# DDR3L.net
KiCad netlist of a schematic drawn in Altium Designer
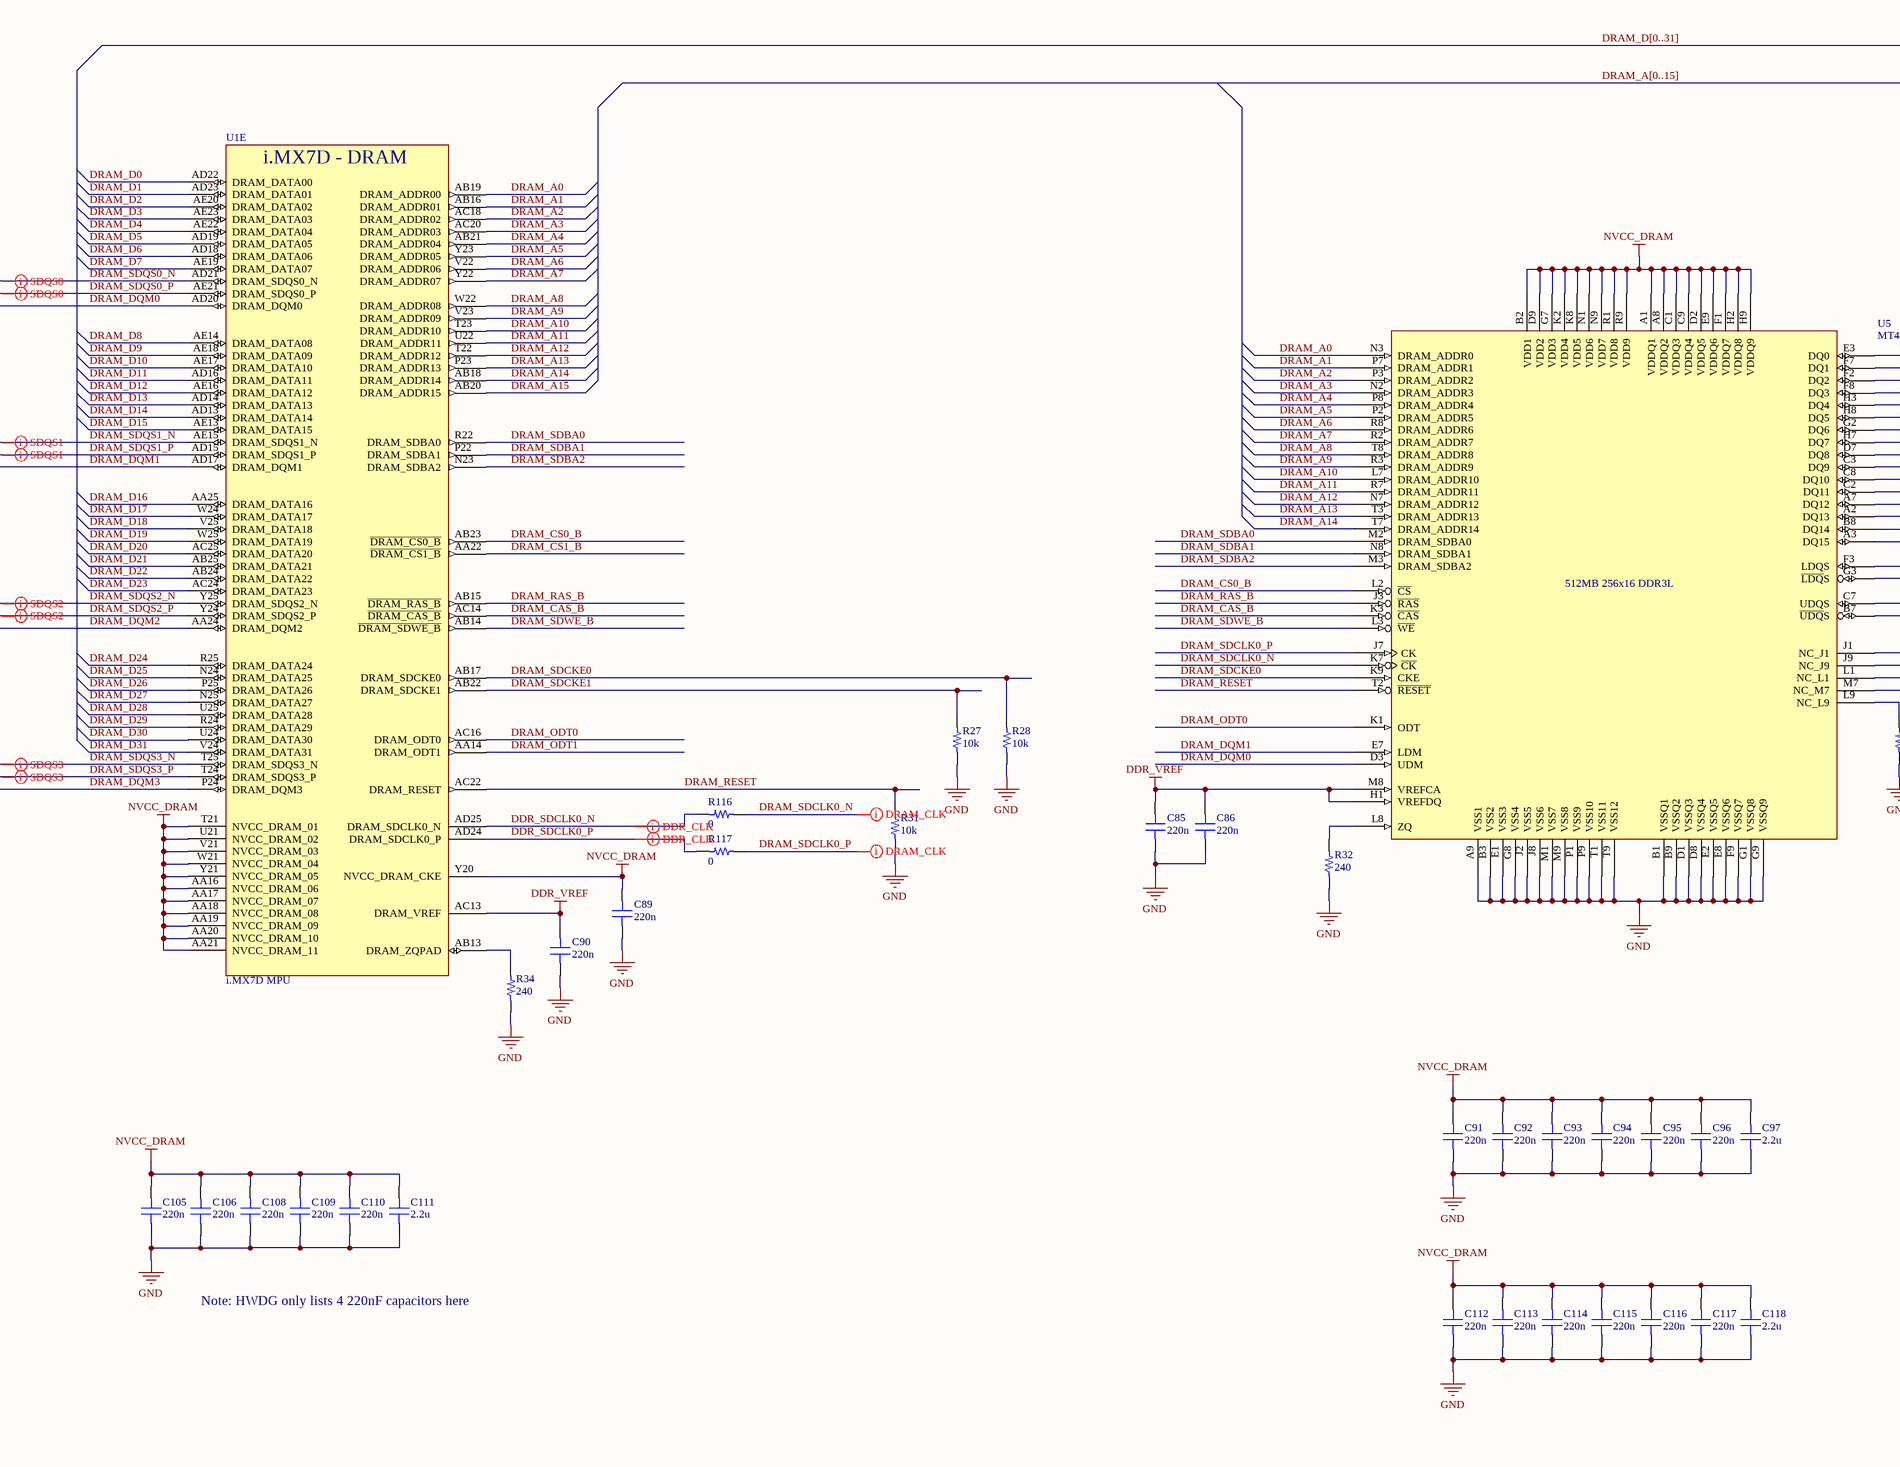
[diagram p0: DDR3L.SchDoc, left]
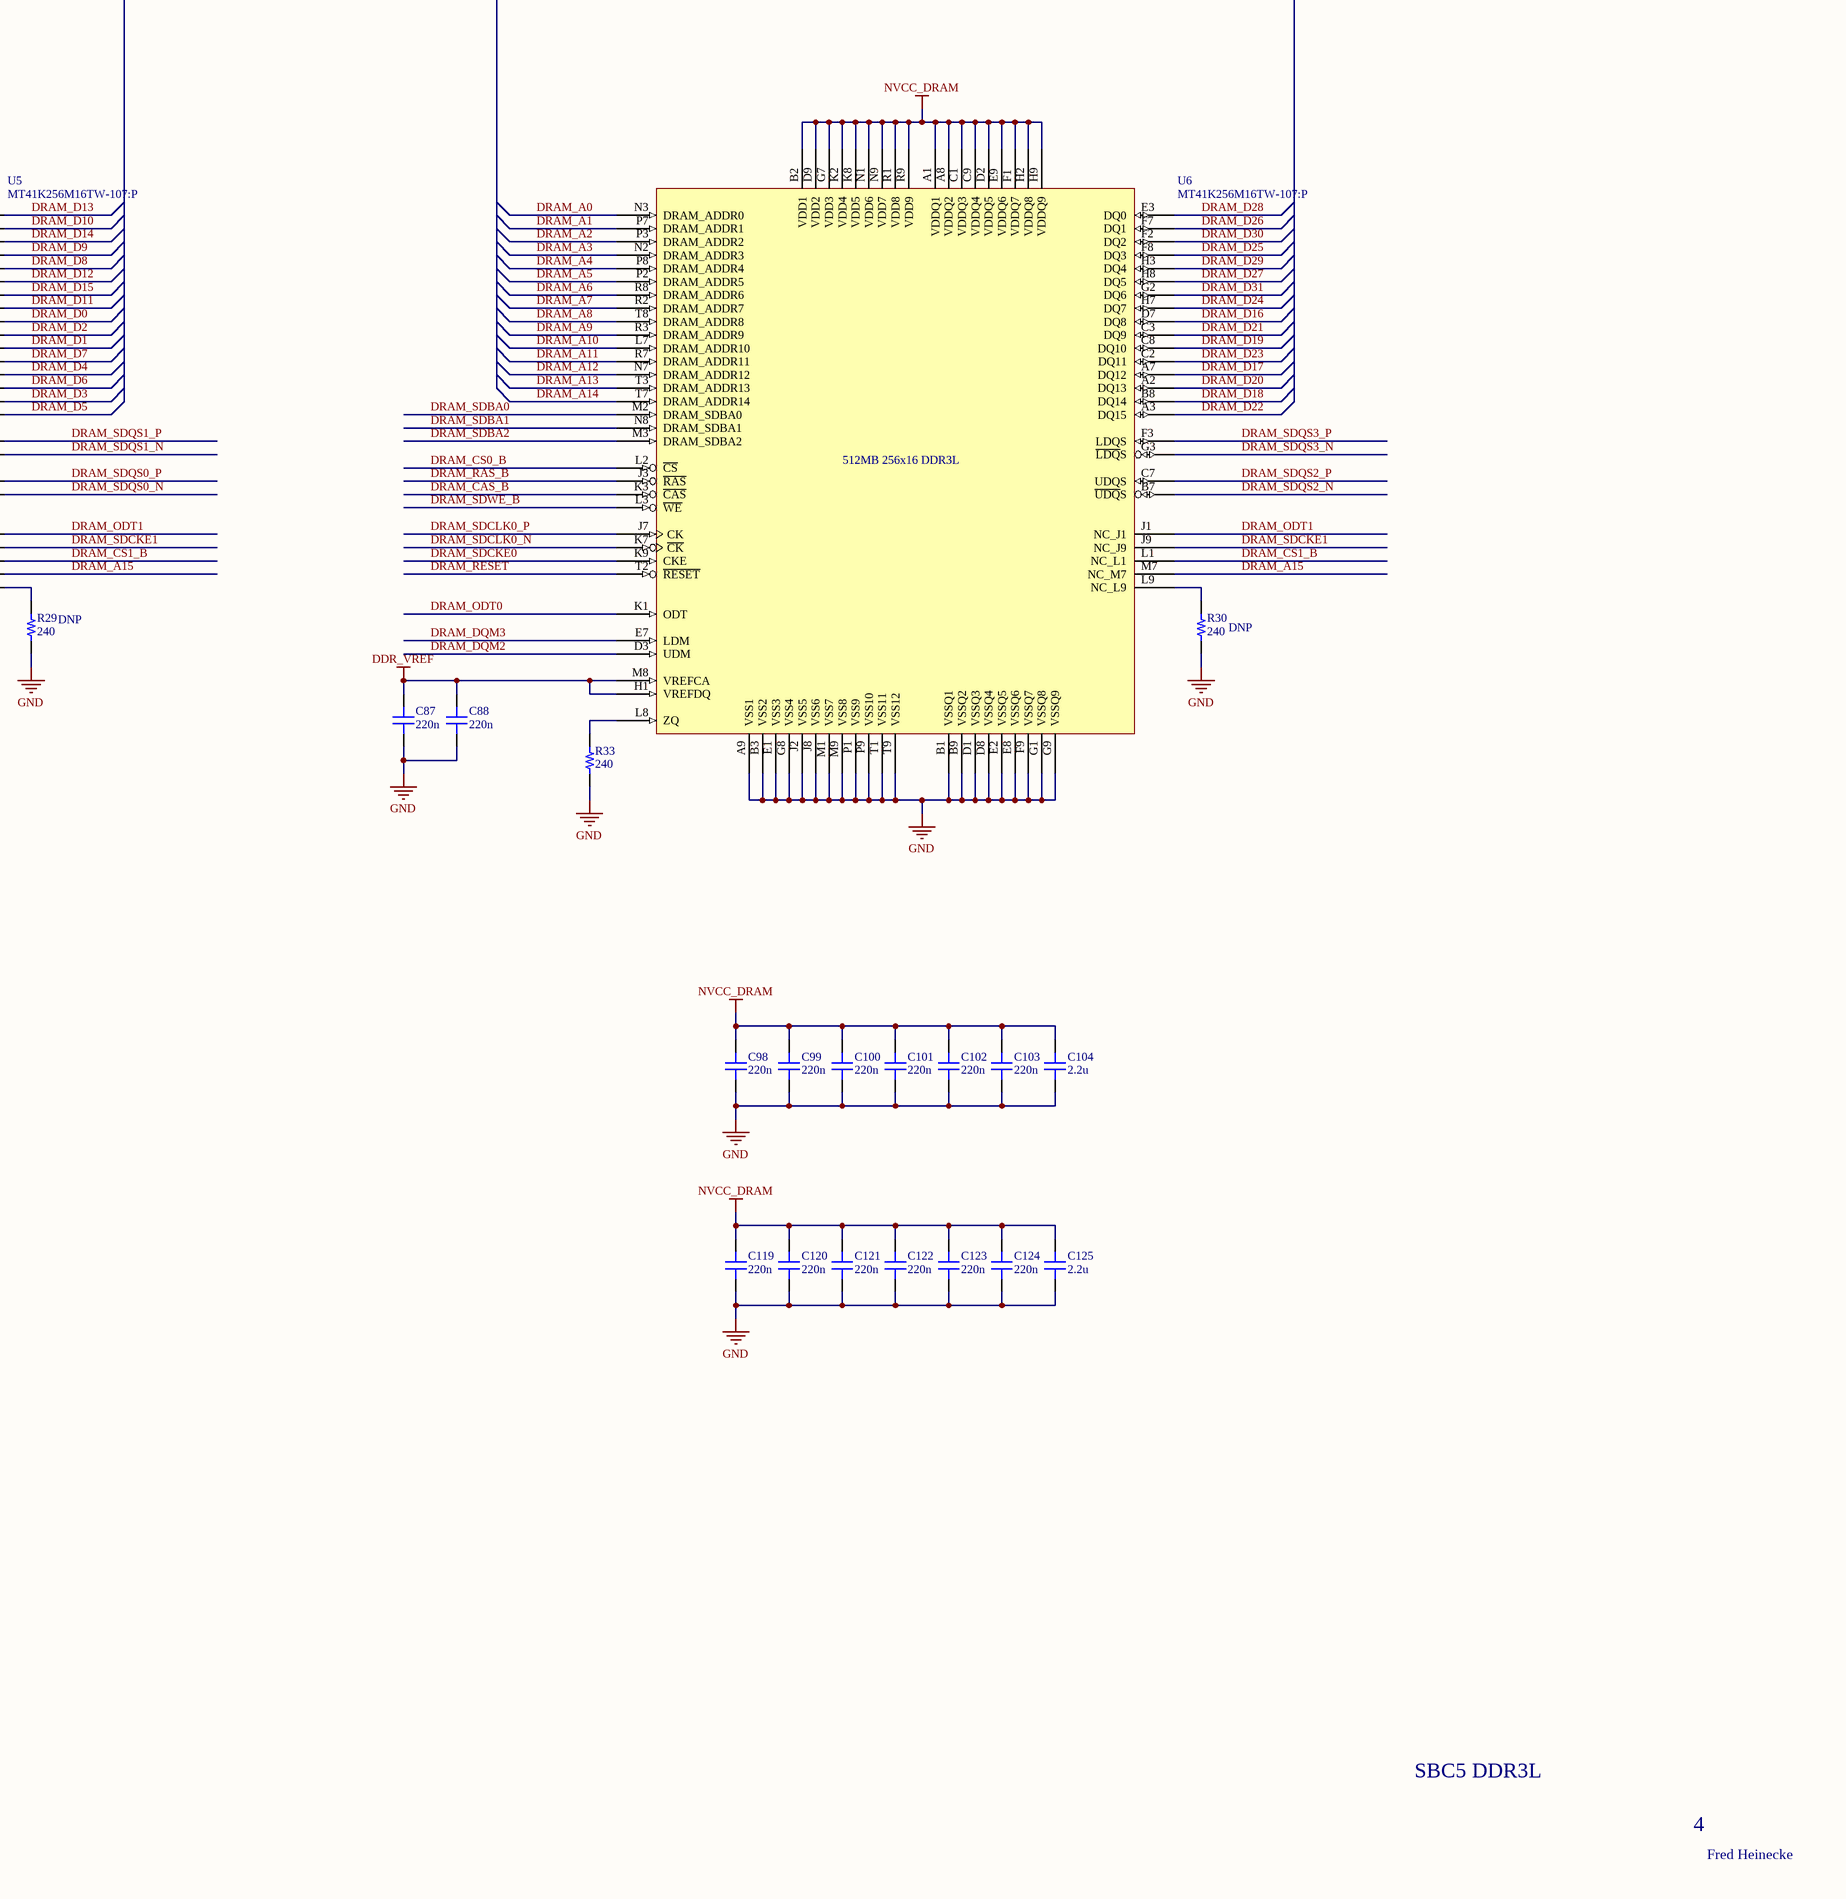
[diagram p1: DDR3L.SchDoc, right]

(export (version "E")
  (design (tool "Eeschema 10.0.6"))
  (components
    (comp (ref "C85")
      (value "220n")
      (footprint "C0201")
      (description "Cap Ceramic Monolithic 0.22uF 16VDC 10% SMD Paper T/R")
      (fields
        (field (name "MANUFACTURER") "Murata")
        (field (name "MANUFACTURER PART NUMBER") "GRM033R61C224KE14D")
      )
      (libsource (lib "SBC5") (part "GRM033R61C224KE14D"))
    )
    (comp (ref "C86")
      (value "220n")
      (footprint "C0201")
      (description "Cap Ceramic Monolithic 0.22uF 16VDC 10% SMD Paper T/R")
      (fields
        (field (name "MANUFACTURER") "Murata")
        (field (name "MANUFACTURER PART NUMBER") "GRM033R61C224KE14D")
      )
      (libsource (lib "SBC5") (part "GRM033R61C224KE14D"))
    )
    (comp (ref "C87")
      (value "220n")
      (footprint "C0201")
      (description "Cap Ceramic Monolithic 0.22uF 16VDC 10% SMD Paper T/R")
      (fields
        (field (name "MANUFACTURER") "Murata")
        (field (name "MANUFACTURER PART NUMBER") "GRM033R61C224KE14D")
      )
      (libsource (lib "SBC5") (part "GRM033R61C224KE14D"))
    )
    (comp (ref "C88")
      (value "220n")
      (footprint "C0201")
      (description "Cap Ceramic Monolithic 0.22uF 16VDC 10% SMD Paper T/R")
      (fields
        (field (name "MANUFACTURER") "Murata")
        (field (name "MANUFACTURER PART NUMBER") "GRM033R61C224KE14D")
      )
      (libsource (lib "SBC5") (part "GRM033R61C224KE14D"))
    )
    (comp (ref "C89")
      (value "220n")
      (footprint "C0201")
      (description "Cap Ceramic Monolithic 0.22uF 16VDC 10% SMD Paper T/R")
      (fields
        (field (name "MANUFACTURER") "Murata")
        (field (name "MANUFACTURER PART NUMBER") "GRM033R61C224KE14D")
      )
      (libsource (lib "SBC5") (part "GRM033R61C224KE14D"))
    )
    (comp (ref "C90")
      (value "220n")
      (footprint "C0201")
      (description "Cap Ceramic Monolithic 0.22uF 16VDC 10% SMD Paper T/R")
      (fields
        (field (name "MANUFACTURER") "Murata")
        (field (name "MANUFACTURER PART NUMBER") "GRM033R61C224KE14D")
      )
      (libsource (lib "SBC5") (part "GRM033R61C224KE14D"))
    )
    (comp (ref "C91")
      (value "220n")
      (footprint "C0201")
      (description "Cap Ceramic Monolithic 0.22uF 16VDC 10% SMD Paper T/R")
      (fields
        (field (name "MANUFACTURER") "Murata")
        (field (name "MANUFACTURER PART NUMBER") "GRM033R61C224KE14D")
      )
      (libsource (lib "SBC5") (part "GRM033R61C224KE14D"))
    )
    (comp (ref "C92")
      (value "220n")
      (footprint "C0201")
      (description "Cap Ceramic Monolithic 0.22uF 16VDC 10% SMD Paper T/R")
      (fields
        (field (name "MANUFACTURER") "Murata")
        (field (name "MANUFACTURER PART NUMBER") "GRM033R61C224KE14D")
      )
      (libsource (lib "SBC5") (part "GRM033R61C224KE14D"))
    )
    (comp (ref "C93")
      (value "220n")
      (footprint "C0201")
      (description "Cap Ceramic Monolithic 0.22uF 16VDC 10% SMD Paper T/R")
      (fields
        (field (name "MANUFACTURER") "Murata")
        (field (name "MANUFACTURER PART NUMBER") "GRM033R61C224KE14D")
      )
      (libsource (lib "SBC5") (part "GRM033R61C224KE14D"))
    )
    (comp (ref "C94")
      (value "220n")
      (footprint "C0201")
      (description "Cap Ceramic Monolithic 0.22uF 16VDC 10% SMD Paper T/R")
      (fields
        (field (name "MANUFACTURER") "Murata")
        (field (name "MANUFACTURER PART NUMBER") "GRM033R61C224KE14D")
      )
      (libsource (lib "SBC5") (part "GRM033R61C224KE14D"))
    )
    (comp (ref "C95")
      (value "220n")
      (footprint "C0201")
      (description "Cap Ceramic Monolithic 0.22uF 16VDC 10% SMD Paper T/R")
      (fields
        (field (name "MANUFACTURER") "Murata")
        (field (name "MANUFACTURER PART NUMBER") "GRM033R61C224KE14D")
      )
      (libsource (lib "SBC5") (part "GRM033R61C224KE14D"))
    )
    (comp (ref "C96")
      (value "220n")
      (footprint "C0201")
      (description "Cap Ceramic Monolithic 0.22uF 16VDC 10% SMD Paper T/R")
      (fields
        (field (name "MANUFACTURER") "Murata")
        (field (name "MANUFACTURER PART NUMBER") "GRM033R61C224KE14D")
      )
      (libsource (lib "SBC5") (part "GRM033R61C224KE14D"))
    )
    (comp (ref "C97")
      (value "2.2u")
      (footprint "C0402")
      (description "TAIYO YUDEN         LMK105BJ225MV-F            CERAMIC CAPACITOR, 2.2UF, 10V, X5R, 20%, 0402")
      (fields
        (field (name "MANUFACTURER") "Taiyo Yuden")
        (field (name "MANUFACTURER PART NUMBER") "LMK105BJ225MV-F")
      )
      (libsource (lib "SBC5") (part "LMK105BJ225MV-F"))
    )
    (comp (ref "C98")
      (value "220n")
      (footprint "C0201")
      (description "Cap Ceramic Monolithic 0.22uF 16VDC 10% SMD Paper T/R")
      (fields
        (field (name "MANUFACTURER") "Murata")
        (field (name "MANUFACTURER PART NUMBER") "GRM033R61C224KE14D")
      )
      (libsource (lib "SBC5") (part "GRM033R61C224KE14D"))
    )
    (comp (ref "C99")
      (value "220n")
      (footprint "C0201")
      (description "Cap Ceramic Monolithic 0.22uF 16VDC 10% SMD Paper T/R")
      (fields
        (field (name "MANUFACTURER") "Murata")
        (field (name "MANUFACTURER PART NUMBER") "GRM033R61C224KE14D")
      )
      (libsource (lib "SBC5") (part "GRM033R61C224KE14D"))
    )
    (comp (ref "C100")
      (value "220n")
      (footprint "C0201")
      (description "Cap Ceramic Monolithic 0.22uF 16VDC 10% SMD Paper T/R")
      (fields
        (field (name "MANUFACTURER") "Murata")
        (field (name "MANUFACTURER PART NUMBER") "GRM033R61C224KE14D")
      )
      (libsource (lib "SBC5") (part "GRM033R61C224KE14D"))
    )
    (comp (ref "C101")
      (value "220n")
      (footprint "C0201")
      (description "Cap Ceramic Monolithic 0.22uF 16VDC 10% SMD Paper T/R")
      (fields
        (field (name "MANUFACTURER") "Murata")
        (field (name "MANUFACTURER PART NUMBER") "GRM033R61C224KE14D")
      )
      (libsource (lib "SBC5") (part "GRM033R61C224KE14D"))
    )
    (comp (ref "C102")
      (value "220n")
      (footprint "C0201")
      (description "Cap Ceramic Monolithic 0.22uF 16VDC 10% SMD Paper T/R")
      (fields
        (field (name "MANUFACTURER") "Murata")
        (field (name "MANUFACTURER PART NUMBER") "GRM033R61C224KE14D")
      )
      (libsource (lib "SBC5") (part "GRM033R61C224KE14D"))
    )
    (comp (ref "C103")
      (value "220n")
      (footprint "C0201")
      (description "Cap Ceramic Monolithic 0.22uF 16VDC 10% SMD Paper T/R")
      (fields
        (field (name "MANUFACTURER") "Murata")
        (field (name "MANUFACTURER PART NUMBER") "GRM033R61C224KE14D")
      )
      (libsource (lib "SBC5") (part "GRM033R61C224KE14D"))
    )
    (comp (ref "C104")
      (value "2.2u")
      (footprint "C0402")
      (description "TAIYO YUDEN         LMK105BJ225MV-F            CERAMIC CAPACITOR, 2.2UF, 10V, X5R, 20%, 0402")
      (fields
        (field (name "MANUFACTURER") "Taiyo Yuden")
        (field (name "MANUFACTURER PART NUMBER") "LMK105BJ225MV-F")
      )
      (libsource (lib "SBC5") (part "LMK105BJ225MV-F"))
    )
    (comp (ref "C105")
      (value "220n")
      (footprint "C0201")
      (description "Cap Ceramic Monolithic 0.22uF 16VDC 10% SMD Paper T/R")
      (fields
        (field (name "MANUFACTURER") "Murata")
        (field (name "MANUFACTURER PART NUMBER") "GRM033R61C224KE14D")
      )
      (libsource (lib "SBC5") (part "GRM033R61C224KE14D"))
    )
    (comp (ref "C106")
      (value "220n")
      (footprint "C0201")
      (description "Cap Ceramic Monolithic 0.22uF 16VDC 10% SMD Paper T/R")
      (fields
        (field (name "MANUFACTURER") "Murata")
        (field (name "MANUFACTURER PART NUMBER") "GRM033R61C224KE14D")
      )
      (libsource (lib "SBC5") (part "GRM033R61C224KE14D"))
    )
    (comp (ref "C108")
      (value "220n")
      (footprint "C0201")
      (description "Cap Ceramic Monolithic 0.22uF 16VDC 10% SMD Paper T/R")
      (fields
        (field (name "MANUFACTURER") "Murata")
        (field (name "MANUFACTURER PART NUMBER") "GRM033R61C224KE14D")
      )
      (libsource (lib "SBC5") (part "GRM033R61C224KE14D"))
    )
    (comp (ref "C109")
      (value "220n")
      (footprint "C0201")
      (description "Cap Ceramic Monolithic 0.22uF 16VDC 10% SMD Paper T/R")
      (fields
        (field (name "MANUFACTURER") "Murata")
        (field (name "MANUFACTURER PART NUMBER") "GRM033R61C224KE14D")
      )
      (libsource (lib "SBC5") (part "GRM033R61C224KE14D"))
    )
    (comp (ref "C110")
      (value "220n")
      (footprint "C0201")
      (description "Cap Ceramic Monolithic 0.22uF 16VDC 10% SMD Paper T/R")
      (fields
        (field (name "MANUFACTURER") "Murata")
        (field (name "MANUFACTURER PART NUMBER") "GRM033R61C224KE14D")
      )
      (libsource (lib "SBC5") (part "GRM033R61C224KE14D"))
    )
    (comp (ref "C111")
      (value "2.2u")
      (footprint "C0402")
      (description "TAIYO YUDEN         LMK105BJ225MV-F            CERAMIC CAPACITOR, 2.2UF, 10V, X5R, 20%, 0402")
      (fields
        (field (name "MANUFACTURER") "Taiyo Yuden")
        (field (name "MANUFACTURER PART NUMBER") "LMK105BJ225MV-F")
      )
      (libsource (lib "SBC5") (part "LMK105BJ225MV-F"))
    )
    (comp (ref "C112")
      (value "220n")
      (footprint "C0201")
      (description "Cap Ceramic Monolithic 0.22uF 16VDC 10% SMD Paper T/R")
      (fields
        (field (name "MANUFACTURER") "Murata")
        (field (name "MANUFACTURER PART NUMBER") "GRM033R61C224KE14D")
      )
      (libsource (lib "SBC5") (part "GRM033R61C224KE14D"))
    )
    (comp (ref "C113")
      (value "220n")
      (footprint "C0201")
      (description "Cap Ceramic Monolithic 0.22uF 16VDC 10% SMD Paper T/R")
      (fields
        (field (name "MANUFACTURER") "Murata")
        (field (name "MANUFACTURER PART NUMBER") "GRM033R61C224KE14D")
      )
      (libsource (lib "SBC5") (part "GRM033R61C224KE14D"))
    )
    (comp (ref "C114")
      (value "220n")
      (footprint "C0201")
      (description "Cap Ceramic Monolithic 0.22uF 16VDC 10% SMD Paper T/R")
      (fields
        (field (name "MANUFACTURER") "Murata")
        (field (name "MANUFACTURER PART NUMBER") "GRM033R61C224KE14D")
      )
      (libsource (lib "SBC5") (part "GRM033R61C224KE14D"))
    )
    (comp (ref "C115")
      (value "220n")
      (footprint "C0201")
      (description "Cap Ceramic Monolithic 0.22uF 16VDC 10% SMD Paper T/R")
      (fields
        (field (name "MANUFACTURER") "Murata")
        (field (name "MANUFACTURER PART NUMBER") "GRM033R61C224KE14D")
      )
      (libsource (lib "SBC5") (part "GRM033R61C224KE14D"))
    )
    (comp (ref "C116")
      (value "220n")
      (footprint "C0201")
      (description "Cap Ceramic Monolithic 0.22uF 16VDC 10% SMD Paper T/R")
      (fields
        (field (name "MANUFACTURER") "Murata")
        (field (name "MANUFACTURER PART NUMBER") "GRM033R61C224KE14D")
      )
      (libsource (lib "SBC5") (part "GRM033R61C224KE14D"))
    )
    (comp (ref "C117")
      (value "220n")
      (footprint "C0201")
      (description "Cap Ceramic Monolithic 0.22uF 16VDC 10% SMD Paper T/R")
      (fields
        (field (name "MANUFACTURER") "Murata")
        (field (name "MANUFACTURER PART NUMBER") "GRM033R61C224KE14D")
      )
      (libsource (lib "SBC5") (part "GRM033R61C224KE14D"))
    )
    (comp (ref "C118")
      (value "2.2u")
      (footprint "C0402")
      (description "TAIYO YUDEN         LMK105BJ225MV-F            CERAMIC CAPACITOR, 2.2UF, 10V, X5R, 20%, 0402")
      (fields
        (field (name "MANUFACTURER") "Taiyo Yuden")
        (field (name "MANUFACTURER PART NUMBER") "LMK105BJ225MV-F")
      )
      (libsource (lib "SBC5") (part "LMK105BJ225MV-F"))
    )
    (comp (ref "C119")
      (value "220n")
      (footprint "C0201")
      (description "Cap Ceramic Monolithic 0.22uF 16VDC 10% SMD Paper T/R")
      (fields
        (field (name "MANUFACTURER") "Murata")
        (field (name "MANUFACTURER PART NUMBER") "GRM033R61C224KE14D")
      )
      (libsource (lib "SBC5") (part "GRM033R61C224KE14D"))
    )
    (comp (ref "C120")
      (value "220n")
      (footprint "C0201")
      (description "Cap Ceramic Monolithic 0.22uF 16VDC 10% SMD Paper T/R")
      (fields
        (field (name "MANUFACTURER") "Murata")
        (field (name "MANUFACTURER PART NUMBER") "GRM033R61C224KE14D")
      )
      (libsource (lib "SBC5") (part "GRM033R61C224KE14D"))
    )
    (comp (ref "C121")
      (value "220n")
      (footprint "C0201")
      (description "Cap Ceramic Monolithic 0.22uF 16VDC 10% SMD Paper T/R")
      (fields
        (field (name "MANUFACTURER") "Murata")
        (field (name "MANUFACTURER PART NUMBER") "GRM033R61C224KE14D")
      )
      (libsource (lib "SBC5") (part "GRM033R61C224KE14D"))
    )
    (comp (ref "C122")
      (value "220n")
      (footprint "C0201")
      (description "Cap Ceramic Monolithic 0.22uF 16VDC 10% SMD Paper T/R")
      (fields
        (field (name "MANUFACTURER") "Murata")
        (field (name "MANUFACTURER PART NUMBER") "GRM033R61C224KE14D")
      )
      (libsource (lib "SBC5") (part "GRM033R61C224KE14D"))
    )
    (comp (ref "C123")
      (value "220n")
      (footprint "C0201")
      (description "Cap Ceramic Monolithic 0.22uF 16VDC 10% SMD Paper T/R")
      (fields
        (field (name "MANUFACTURER") "Murata")
        (field (name "MANUFACTURER PART NUMBER") "GRM033R61C224KE14D")
      )
      (libsource (lib "SBC5") (part "GRM033R61C224KE14D"))
    )
    (comp (ref "C124")
      (value "220n")
      (footprint "C0201")
      (description "Cap Ceramic Monolithic 0.22uF 16VDC 10% SMD Paper T/R")
      (fields
        (field (name "MANUFACTURER") "Murata")
        (field (name "MANUFACTURER PART NUMBER") "GRM033R61C224KE14D")
      )
      (libsource (lib "SBC5") (part "GRM033R61C224KE14D"))
    )
    (comp (ref "C125")
      (value "2.2u")
      (footprint "C0402")
      (description "TAIYO YUDEN         LMK105BJ225MV-F            CERAMIC CAPACITOR, 2.2UF, 10V, X5R, 20%, 0402")
      (fields
        (field (name "MANUFACTURER") "Taiyo Yuden")
        (field (name "MANUFACTURER PART NUMBER") "LMK105BJ225MV-F")
      )
      (libsource (lib "SBC5") (part "LMK105BJ225MV-F"))
    )
    (comp (ref "R27")
      (value "10k")
      (footprint "R0201")
      (description "RES 10K OHM 1% 1/20W 0201")
      (fields
        (field (name "MANUFACTURER") "Stackpole Electronics")
        (field (name "MANUFACTURER PART NUMBER") "RMCF0201FT10K0")
      )
      (libsource (lib "SBC5") (part "RMCF0201FT10K0"))
    )
    (comp (ref "R28")
      (value "10k")
      (footprint "R0201")
      (description "RES 10K OHM 1% 1/20W 0201")
      (fields
        (field (name "MANUFACTURER") "Stackpole Electronics")
        (field (name "MANUFACTURER PART NUMBER") "RMCF0201FT10K0")
      )
      (libsource (lib "SBC5") (part "RMCF0201FT10K0"))
    )
    (comp (ref "R29")
      (value "240")
      (footprint "R0201")
      (description "RES 240 OHM 1% 1/20W 0201")
      (fields
        (field (name "MANUFACTURER") "Stackpole Electronics")
        (field (name "MANUFACTURER PART NUMBER") "RMCF0201FG240R")
      )
      (libsource (lib "SBC5") (part "RMCF0201FG240R"))
    )
    (comp (ref "R30")
      (value "240")
      (footprint "R0201")
      (description "RES 240 OHM 1% 1/20W 0201")
      (fields
        (field (name "MANUFACTURER") "Stackpole Electronics")
        (field (name "MANUFACTURER PART NUMBER") "RMCF0201FG240R")
      )
      (libsource (lib "SBC5") (part "RMCF0201FG240R"))
    )
    (comp (ref "R31")
      (value "10k")
      (footprint "R0201")
      (description "RES 10K OHM 1% 1/20W 0201")
      (fields
        (field (name "MANUFACTURER") "Stackpole Electronics")
        (field (name "MANUFACTURER PART NUMBER") "RMCF0201FT10K0")
      )
      (libsource (lib "SBC5") (part "RMCF0201FT10K0"))
    )
    (comp (ref "R32")
      (value "240")
      (footprint "R0201")
      (description "RES 240 OHM 1% 1/20W 0201")
      (fields
        (field (name "MANUFACTURER") "Stackpole Electronics")
        (field (name "MANUFACTURER PART NUMBER") "RMCF0201FG240R")
      )
      (libsource (lib "SBC5") (part "RMCF0201FG240R"))
    )
    (comp (ref "R33")
      (value "240")
      (footprint "R0201")
      (description "RES 240 OHM 1% 1/20W 0201")
      (fields
        (field (name "MANUFACTURER") "Stackpole Electronics")
        (field (name "MANUFACTURER PART NUMBER") "RMCF0201FG240R")
      )
      (libsource (lib "SBC5") (part "RMCF0201FG240R"))
    )
    (comp (ref "R34")
      (value "240")
      (footprint "R0201")
      (description "RES 240 OHM 1% 1/20W 0201")
      (fields
        (field (name "MANUFACTURER") "Stackpole Electronics")
        (field (name "MANUFACTURER PART NUMBER") "RMCF0201FG240R")
      )
      (libsource (lib "SBC5") (part "RMCF0201FG240R"))
    )
    (comp (ref "R116")
      (value "0")
      (footprint "R0201")
      (description "ERJ Series 0201 0 Ohm 0.05 W Jumper Surface Mount Thick Film Chip Resistor")
      (fields
        (field (name "MANUFACTURER") "Panasonic")
        (field (name "MANUFACTURER PART NUMBER") "ERJ-1GN0R00C")
      )
      (libsource (lib "SBC5") (part "ERJ-1GN0R00C"))
    )
    (comp (ref "R117")
      (value "0")
      (footprint "R0201")
      (description "ERJ Series 0201 0 Ohm 0.05 W Jumper Surface Mount Thick Film Chip Resistor")
      (fields
        (field (name "MANUFACTURER") "Panasonic")
        (field (name "MANUFACTURER PART NUMBER") "ERJ-1GN0R00C")
      )
      (libsource (lib "SBC5") (part "ERJ-1GN0R00C"))
    )
    (comp (ref "U1")
      (value "i.MX7D MPU")
      (footprint "BGA541C75P25X25_1900X1900X140")
      (description "Heterogeneous Multicore Processing Architecture")
      (fields
        (field (name "MANUFACTURER") "NXP Freescale")
        (field (name "MANUFACTURER PART NUMBER") "MCIMX7D2DVM12SD")
      )
      (libsource (lib "SBC5") (part "MCIMX7D2DVM12SD"))
    )
    (comp (ref "U5")
      (value "MT41K256M16TW-107:P")
      (footprint "96xBGA DDR3L")
      (description "DRAM Chip DDR3L SDRAM 4G-Bit 256Mx16 1.35V 96 FBGA")
      (fields (field (name "MANUFACTURER") "Micron Technology"))
      (libsource (lib "SBC5") (part "MT41K256M16TW-107{colon}P"))
    )
    (comp (ref "U6")
      (value "MT41K256M16TW-107:P")
      (footprint "96xBGA DDR3L")
      (description "DRAM Chip DDR3L SDRAM 4G-Bit 256Mx16 1.35V 96 FBGA")
      (fields (field (name "MANUFACTURER") "Micron Technology"))
      (libsource (lib "SBC5") (part "MT41K256M16TW-107{colon}P"))
    )
  )
  (nets
    (net (code "1") (name "/DDR_SDCLK0_N") (class "Default")
      (node (ref "R116") (pin "1") (pinfunction "1_1") (pintype "passive"))
      (node (ref "U1") (pin "AD25") (pinfunction "DRAM_SDCLK0_N_AD25") (pintype "passive"))
    )
    (net (code "2") (name "/DDR_SDCLK0_P") (class "Default")
      (node (ref "R117") (pin "1") (pinfunction "1_1") (pintype "passive"))
      (node (ref "U1") (pin "AD24") (pinfunction "DRAM_SDCLK0_P_AD24") (pintype "passive"))
    )
    (net (code "3") (name "/DRAM_A0") (class "Default")
      (node (ref "U1") (pin "AB19") (pinfunction "DRAM_ADDR00_AB19") (pintype "output"))
      (node (ref "U5") (pin "N3") (pinfunction "DRAM_ADDR0_N3") (pintype "input"))
      (node (ref "U6") (pin "N3") (pinfunction "DRAM_ADDR0_N3") (pintype "input"))
    )
    (net (code "4") (name "/DRAM_A1") (class "Default")
      (node (ref "U1") (pin "AB16") (pinfunction "DRAM_ADDR01_AB16") (pintype "output"))
      (node (ref "U5") (pin "P7") (pinfunction "DRAM_ADDR1_P7") (pintype "input"))
      (node (ref "U6") (pin "P7") (pinfunction "DRAM_ADDR1_P7") (pintype "input"))
    )
    (net (code "5") (name "/DRAM_A2") (class "Default")
      (node (ref "U1") (pin "AC18") (pinfunction "DRAM_ADDR02_AC18") (pintype "output"))
      (node (ref "U5") (pin "P3") (pinfunction "DRAM_ADDR2_P3") (pintype "input"))
      (node (ref "U6") (pin "P3") (pinfunction "DRAM_ADDR2_P3") (pintype "input"))
    )
    (net (code "6") (name "/DRAM_A3") (class "Default")
      (node (ref "U1") (pin "AC20") (pinfunction "DRAM_ADDR03_AC20") (pintype "output"))
      (node (ref "U5") (pin "N2") (pinfunction "DRAM_ADDR3_N2") (pintype "input"))
      (node (ref "U6") (pin "N2") (pinfunction "DRAM_ADDR3_N2") (pintype "input"))
    )
    (net (code "7") (name "/DRAM_A4") (class "Default")
      (node (ref "U1") (pin "AB21") (pinfunction "DRAM_ADDR04_AB21") (pintype "output"))
      (node (ref "U5") (pin "P8") (pinfunction "DRAM_ADDR4_P8") (pintype "input"))
      (node (ref "U6") (pin "P8") (pinfunction "DRAM_ADDR4_P8") (pintype "input"))
    )
    (net (code "8") (name "/DRAM_A5") (class "Default")
      (node (ref "U1") (pin "Y23") (pinfunction "DRAM_ADDR05_Y23") (pintype "output"))
      (node (ref "U5") (pin "P2") (pinfunction "DRAM_ADDR5_P2") (pintype "input"))
      (node (ref "U6") (pin "P2") (pinfunction "DRAM_ADDR5_P2") (pintype "input"))
    )
    (net (code "9") (name "/DRAM_A6") (class "Default")
      (node (ref "U1") (pin "V22") (pinfunction "DRAM_ADDR06_V22") (pintype "output"))
      (node (ref "U5") (pin "R8") (pinfunction "DRAM_ADDR6_R8") (pintype "input"))
      (node (ref "U6") (pin "R8") (pinfunction "DRAM_ADDR6_R8") (pintype "input"))
    )
    (net (code "10") (name "/DRAM_A7") (class "Default")
      (node (ref "U1") (pin "Y22") (pinfunction "DRAM_ADDR07_Y22") (pintype "output"))
      (node (ref "U5") (pin "R2") (pinfunction "DRAM_ADDR7_R2") (pintype "input"))
      (node (ref "U6") (pin "R2") (pinfunction "DRAM_ADDR7_R2") (pintype "input"))
    )
    (net (code "11") (name "/DRAM_A8") (class "Default")
      (node (ref "U1") (pin "W22") (pinfunction "DRAM_ADDR08_W22") (pintype "output"))
      (node (ref "U5") (pin "T8") (pinfunction "DRAM_ADDR8_T8") (pintype "input"))
      (node (ref "U6") (pin "T8") (pinfunction "DRAM_ADDR8_T8") (pintype "input"))
    )
    (net (code "12") (name "/DRAM_A9") (class "Default")
      (node (ref "U1") (pin "V23") (pinfunction "DRAM_ADDR09_V23") (pintype "output"))
      (node (ref "U5") (pin "R3") (pinfunction "DRAM_ADDR9_R3") (pintype "input"))
      (node (ref "U6") (pin "R3") (pinfunction "DRAM_ADDR9_R3") (pintype "input"))
    )
    (net (code "13") (name "/DRAM_A10") (class "Default")
      (node (ref "U1") (pin "T23") (pinfunction "DRAM_ADDR10_T23") (pintype "output"))
      (node (ref "U5") (pin "L7") (pinfunction "DRAM_ADDR10_L7") (pintype "input"))
      (node (ref "U6") (pin "L7") (pinfunction "DRAM_ADDR10_L7") (pintype "input"))
    )
    (net (code "14") (name "/DRAM_A11") (class "Default")
      (node (ref "U1") (pin "U22") (pinfunction "DRAM_ADDR11_U22") (pintype "output"))
      (node (ref "U5") (pin "R7") (pinfunction "DRAM_ADDR11_R7") (pintype "input"))
      (node (ref "U6") (pin "R7") (pinfunction "DRAM_ADDR11_R7") (pintype "input"))
    )
    (net (code "15") (name "/DRAM_A12") (class "Default")
      (node (ref "U1") (pin "T22") (pinfunction "DRAM_ADDR12_T22") (pintype "output"))
      (node (ref "U5") (pin "N7") (pinfunction "DRAM_ADDR12_N7") (pintype "input"))
      (node (ref "U6") (pin "N7") (pinfunction "DRAM_ADDR12_N7") (pintype "input"))
    )
    (net (code "16") (name "/DRAM_A13") (class "Default")
      (node (ref "U1") (pin "P23") (pinfunction "DRAM_ADDR13_P23") (pintype "output"))
      (node (ref "U5") (pin "T3") (pinfunction "DRAM_ADDR13_T3") (pintype "input"))
      (node (ref "U6") (pin "T3") (pinfunction "DRAM_ADDR13_T3") (pintype "input"))
    )
    (net (code "17") (name "/DRAM_A14") (class "Default")
      (node (ref "U1") (pin "AB18") (pinfunction "DRAM_ADDR14_AB18") (pintype "output"))
      (node (ref "U5") (pin "T7") (pinfunction "DRAM_ADDR14_T7") (pintype "input"))
      (node (ref "U6") (pin "T7") (pinfunction "DRAM_ADDR14_T7") (pintype "input"))
    )
    (net (code "18") (name "/DRAM_A15") (class "Default")
      (node (ref "U1") (pin "AB20") (pinfunction "DRAM_ADDR15_AB20") (pintype "output"))
      (node (ref "U5") (pin "M7") (pinfunction "NC_M7_M7") (pintype "passive"))
      (node (ref "U6") (pin "M7") (pinfunction "NC_M7_M7") (pintype "passive"))
    )
    (net (code "20") (name "/DRAM_CAS_B") (class "Default")
      (node (ref "U1") (pin "AC14") (pinfunction "~{DRAM_CAS_B}_AC14") (pintype "output"))
      (node (ref "U5") (pin "K3") (pinfunction "~{CAS}_K3") (pintype "input"))
      (node (ref "U6") (pin "K3") (pinfunction "~{CAS}_K3") (pintype "input"))
    )
    (net (code "21") (name "/DRAM_CS0_B") (class "Default")
      (node (ref "U1") (pin "AB23") (pinfunction "~{DRAM_CS0_B}_AB23") (pintype "output"))
      (node (ref "U5") (pin "L2") (pinfunction "~{CS}_L2") (pintype "input"))
      (node (ref "U6") (pin "L2") (pinfunction "~{CS}_L2") (pintype "input"))
    )
    (net (code "22") (name "/DRAM_CS1_B") (class "Default")
      (node (ref "U1") (pin "AA22") (pinfunction "~{DRAM_CS1_B}_AA22") (pintype "output"))
      (node (ref "U5") (pin "L1") (pinfunction "NC_L1_L1") (pintype "passive"))
      (node (ref "U6") (pin "L1") (pinfunction "NC_L1_L1") (pintype "passive"))
    )
    (net (code "23") (name "/DRAM_D0") (class "Default")
      (node (ref "U1") (pin "AD22") (pinfunction "DRAM_DATA00_AD22") (pintype "bidirectional"))
      (node (ref "U5") (pin "D7") (pinfunction "DQ8_D7") (pintype "bidirectional"))
    )
    (net (code "24") (name "/DRAM_D1") (class "Default")
      (node (ref "U1") (pin "AD23") (pinfunction "DRAM_DATA01_AD23") (pintype "bidirectional"))
      (node (ref "U5") (pin "C8") (pinfunction "DQ10_C8") (pintype "bidirectional"))
    )
    (net (code "25") (name "/DRAM_D2") (class "Default")
      (node (ref "U1") (pin "AE20") (pinfunction "DRAM_DATA02_AE20") (pintype "bidirectional"))
      (node (ref "U5") (pin "C3") (pinfunction "DQ9_C3") (pintype "bidirectional"))
    )
    (net (code "26") (name "/DRAM_D3") (class "Default")
      (node (ref "U1") (pin "AE23") (pinfunction "DRAM_DATA03_AE23") (pintype "bidirectional"))
      (node (ref "U5") (pin "B8") (pinfunction "DQ14_B8") (pintype "bidirectional"))
    )
    (net (code "27") (name "/DRAM_D4") (class "Default")
      (node (ref "U1") (pin "AE22") (pinfunction "DRAM_DATA04_AE22") (pintype "bidirectional"))
      (node (ref "U5") (pin "A7") (pinfunction "DQ12_A7") (pintype "bidirectional"))
    )
    (net (code "28") (name "/DRAM_D5") (class "Default")
      (node (ref "U1") (pin "AD19") (pinfunction "DRAM_DATA05_AD19") (pintype "bidirectional"))
      (node (ref "U5") (pin "A3") (pinfunction "DQ15_A3") (pintype "bidirectional"))
    )
    (net (code "29") (name "/DRAM_D6") (class "Default")
      (node (ref "U1") (pin "AD18") (pinfunction "DRAM_DATA06_AD18") (pintype "bidirectional"))
      (node (ref "U5") (pin "A2") (pinfunction "DQ13_A2") (pintype "bidirectional"))
    )
    (net (code "30") (name "/DRAM_D7") (class "Default")
      (node (ref "U1") (pin "AE19") (pinfunction "DRAM_DATA07_AE19") (pintype "bidirectional"))
      (node (ref "U5") (pin "C2") (pinfunction "DQ11_C2") (pintype "bidirectional"))
    )
    (net (code "31") (name "/DRAM_D8") (class "Default")
      (node (ref "U1") (pin "AE14") (pinfunction "DRAM_DATA08_AE14") (pintype "bidirectional"))
      (node (ref "U5") (pin "H3") (pinfunction "DQ4_H3") (pintype "bidirectional"))
    )
    (net (code "32") (name "/DRAM_D9") (class "Default")
      (node (ref "U1") (pin "AE18") (pinfunction "DRAM_DATA09_AE18") (pintype "bidirectional"))
      (node (ref "U5") (pin "F8") (pinfunction "DQ3_F8") (pintype "bidirectional"))
    )
    (net (code "33") (name "/DRAM_D10") (class "Default")
      (node (ref "U1") (pin "AE17") (pinfunction "DRAM_DATA10_AE17") (pintype "bidirectional"))
      (node (ref "U5") (pin "F7") (pinfunction "DQ1_F7") (pintype "bidirectional"))
    )
    (net (code "34") (name "/DRAM_D11") (class "Default")
      (node (ref "U1") (pin "AD16") (pinfunction "DRAM_DATA11_AD16") (pintype "bidirectional"))
      (node (ref "U5") (pin "H7") (pinfunction "DQ7_H7") (pintype "bidirectional"))
    )
    (net (code "35") (name "/DRAM_D12") (class "Default")
      (node (ref "U1") (pin "AE16") (pinfunction "DRAM_DATA12_AE16") (pintype "bidirectional"))
      (node (ref "U5") (pin "H8") (pinfunction "DQ5_H8") (pintype "bidirectional"))
    )
    (net (code "36") (name "/DRAM_D13") (class "Default")
      (node (ref "U1") (pin "AD14") (pinfunction "DRAM_DATA13_AD14") (pintype "bidirectional"))
      (node (ref "U5") (pin "E3") (pinfunction "DQ0_E3") (pintype "bidirectional"))
    )
    (net (code "37") (name "/DRAM_D14") (class "Default")
      (node (ref "U1") (pin "AD13") (pinfunction "DRAM_DATA14_AD13") (pintype "bidirectional"))
      (node (ref "U5") (pin "F2") (pinfunction "DQ2_F2") (pintype "bidirectional"))
    )
    (net (code "38") (name "/DRAM_D15") (class "Default")
      (node (ref "U1") (pin "AE13") (pinfunction "DRAM_DATA15_AE13") (pintype "bidirectional"))
      (node (ref "U5") (pin "G2") (pinfunction "DQ6_G2") (pintype "bidirectional"))
    )
    (net (code "39") (name "/DRAM_D16") (class "Default")
      (node (ref "U1") (pin "AA25") (pinfunction "DRAM_DATA16_AA25") (pintype "bidirectional"))
      (node (ref "U6") (pin "D7") (pinfunction "DQ8_D7") (pintype "bidirectional"))
    )
    (net (code "40") (name "/DRAM_D17") (class "Default")
      (node (ref "U1") (pin "W24") (pinfunction "DRAM_DATA17_W24") (pintype "bidirectional"))
      (node (ref "U6") (pin "A7") (pinfunction "DQ12_A7") (pintype "bidirectional"))
    )
    (net (code "41") (name "/DRAM_D18") (class "Default")
      (node (ref "U1") (pin "V25") (pinfunction "DRAM_DATA18_V25") (pintype "bidirectional"))
      (node (ref "U6") (pin "B8") (pinfunction "DQ14_B8") (pintype "bidirectional"))
    )
    (net (code "42") (name "/DRAM_D19") (class "Default")
      (node (ref "U1") (pin "W25") (pinfunction "DRAM_DATA19_W25") (pintype "bidirectional"))
      (node (ref "U6") (pin "C8") (pinfunction "DQ10_C8") (pintype "bidirectional"))
    )
    (net (code "43") (name "/DRAM_D20") (class "Default")
      (node (ref "U1") (pin "AC25") (pinfunction "DRAM_DATA20_AC25") (pintype "bidirectional"))
      (node (ref "U6") (pin "A2") (pinfunction "DQ13_A2") (pintype "bidirectional"))
    )
    (net (code "44") (name "/DRAM_D21") (class "Default")
      (node (ref "U1") (pin "AB25") (pinfunction "DRAM_DATA21_AB25") (pintype "bidirectional"))
      (node (ref "U6") (pin "C3") (pinfunction "DQ9_C3") (pintype "bidirectional"))
    )
    (net (code "45") (name "/DRAM_D22") (class "Default")
      (node (ref "U1") (pin "AB24") (pinfunction "DRAM_DATA22_AB24") (pintype "bidirectional"))
      (node (ref "U6") (pin "A3") (pinfunction "DQ15_A3") (pintype "bidirectional"))
    )
    (net (code "46") (name "/DRAM_D23") (class "Default")
      (node (ref "U1") (pin "AC24") (pinfunction "DRAM_DATA23_AC24") (pintype "bidirectional"))
      (node (ref "U6") (pin "C2") (pinfunction "DQ11_C2") (pintype "bidirectional"))
    )
    (net (code "47") (name "/DRAM_D24") (class "Default")
      (node (ref "U1") (pin "R25") (pinfunction "DRAM_DATA24_R25") (pintype "bidirectional"))
      (node (ref "U6") (pin "H7") (pinfunction "DQ7_H7") (pintype "bidirectional"))
    )
    (net (code "48") (name "/DRAM_D25") (class "Default")
      (node (ref "U1") (pin "N24") (pinfunction "DRAM_DATA25_N24") (pintype "bidirectional"))
      (node (ref "U6") (pin "F8") (pinfunction "DQ3_F8") (pintype "bidirectional"))
    )
    (net (code "49") (name "/DRAM_D26") (class "Default")
      (node (ref "U1") (pin "P25") (pinfunction "DRAM_DATA26_P25") (pintype "bidirectional"))
      (node (ref "U6") (pin "F7") (pinfunction "DQ1_F7") (pintype "bidirectional"))
    )
    (net (code "50") (name "/DRAM_D27") (class "Default")
      (node (ref "U1") (pin "N25") (pinfunction "DRAM_DATA27_N25") (pintype "bidirectional"))
      (node (ref "U6") (pin "H8") (pinfunction "DQ5_H8") (pintype "bidirectional"))
    )
    (net (code "51") (name "/DRAM_D28") (class "Default")
      (node (ref "U1") (pin "U25") (pinfunction "DRAM_DATA28_U25") (pintype "bidirectional"))
      (node (ref "U6") (pin "E3") (pinfunction "DQ0_E3") (pintype "bidirectional"))
    )
    (net (code "52") (name "/DRAM_D29") (class "Default")
      (node (ref "U1") (pin "R24") (pinfunction "DRAM_DATA29_R24") (pintype "bidirectional"))
      (node (ref "U6") (pin "H3") (pinfunction "DQ4_H3") (pintype "bidirectional"))
    )
    (net (code "53") (name "/DRAM_D30") (class "Default")
      (node (ref "U1") (pin "U24") (pinfunction "DRAM_DATA30_U24") (pintype "bidirectional"))
      (node (ref "U6") (pin "F2") (pinfunction "DQ2_F2") (pintype "bidirectional"))
    )
    (net (code "54") (name "/DRAM_D31") (class "Default")
      (node (ref "U1") (pin "V24") (pinfunction "DRAM_DATA31_V24") (pintype "bidirectional"))
      (node (ref "U6") (pin "G2") (pinfunction "DQ6_G2") (pintype "bidirectional"))
    )
    (net (code "55") (name "/DRAM_DQM0") (class "Default")
      (node (ref "U1") (pin "AD20") (pinfunction "DRAM_DQM0_AD20") (pintype "bidirectional"))
      (node (ref "U5") (pin "D3") (pinfunction "UDM_D3") (pintype "input"))
    )
    (net (code "56") (name "/DRAM_DQM1") (class "Default")
      (node (ref "U1") (pin "AD17") (pinfunction "DRAM_DQM1_AD17") (pintype "bidirectional"))
      (node (ref "U5") (pin "E7") (pinfunction "LDM_E7") (pintype "input"))
    )
    (net (code "57") (name "/DRAM_DQM2") (class "Default")
      (node (ref "U1") (pin "AA24") (pinfunction "DRAM_DQM2_AA24") (pintype "bidirectional"))
      (node (ref "U6") (pin "D3") (pinfunction "UDM_D3") (pintype "input"))
    )
    (net (code "58") (name "/DRAM_DQM3") (class "Default")
      (node (ref "U1") (pin "P24") (pinfunction "DRAM_DQM3_P24") (pintype "bidirectional"))
      (node (ref "U6") (pin "E7") (pinfunction "LDM_E7") (pintype "input"))
    )
    (net (code "60") (name "/DRAM_ODT0") (class "Default")
      (node (ref "U1") (pin "AC16") (pinfunction "DRAM_ODT0_AC16") (pintype "output"))
      (node (ref "U5") (pin "K1") (pinfunction "ODT_K1") (pintype "input"))
      (node (ref "U6") (pin "K1") (pinfunction "ODT_K1") (pintype "input"))
    )
    (net (code "61") (name "/DRAM_ODT1") (class "Default")
      (node (ref "U1") (pin "AA14") (pinfunction "DRAM_ODT1_AA14") (pintype "output"))
      (node (ref "U5") (pin "J1") (pinfunction "NC_J1_J1") (pintype "passive"))
      (node (ref "U6") (pin "J1") (pinfunction "NC_J1_J1") (pintype "passive"))
    )
    (net (code "62") (name "/DRAM_RAS_B") (class "Default")
      (node (ref "U1") (pin "AB15") (pinfunction "~{DRAM_RAS_B}_AB15") (pintype "output"))
      (node (ref "U5") (pin "J3") (pinfunction "~{RAS}_J3") (pintype "input"))
      (node (ref "U6") (pin "J3") (pinfunction "~{RAS}_J3") (pintype "input"))
    )
    (net (code "63") (name "/DRAM_RESET") (class "Default")
      (node (ref "R31") (pin "2") (pinfunction "2_2") (pintype "passive"))
      (node (ref "U1") (pin "AC22") (pinfunction "DRAM_RESET_AC22") (pintype "output"))
      (node (ref "U5") (pin "T2") (pinfunction "~{RESET}_T2") (pintype "input"))
      (node (ref "U6") (pin "T2") (pinfunction "~{RESET}_T2") (pintype "input"))
    )
    (net (code "64") (name "/DRAM_SDBA0") (class "Default")
      (node (ref "U1") (pin "R22") (pinfunction "DRAM_SDBA0_R22") (pintype "output"))
      (node (ref "U5") (pin "M2") (pinfunction "DRAM_SDBA0_M2") (pintype "input"))
      (node (ref "U6") (pin "M2") (pinfunction "DRAM_SDBA0_M2") (pintype "input"))
    )
    (net (code "65") (name "/DRAM_SDBA1") (class "Default")
      (node (ref "U1") (pin "P22") (pinfunction "DRAM_SDBA1_P22") (pintype "output"))
      (node (ref "U5") (pin "N8") (pinfunction "DRAM_SDBA1_N8") (pintype "input"))
      (node (ref "U6") (pin "N8") (pinfunction "DRAM_SDBA1_N8") (pintype "input"))
    )
    (net (code "66") (name "/DRAM_SDBA2") (class "Default")
      (node (ref "U1") (pin "N23") (pinfunction "DRAM_SDBA2_N23") (pintype "output"))
      (node (ref "U5") (pin "M3") (pinfunction "DRAM_SDBA2_M3") (pintype "input"))
      (node (ref "U6") (pin "M3") (pinfunction "DRAM_SDBA2_M3") (pintype "input"))
    )
    (net (code "67") (name "/DRAM_SDCKE0") (class "Default")
      (node (ref "R28") (pin "2") (pinfunction "2_2") (pintype "passive"))
      (node (ref "U1") (pin "AB17") (pinfunction "DRAM_SDCKE0_AB17") (pintype "output"))
      (node (ref "U5") (pin "K9") (pinfunction "CKE_K9") (pintype "input"))
      (node (ref "U6") (pin "K9") (pinfunction "CKE_K9") (pintype "input"))
    )
    (net (code "68") (name "/DRAM_SDCKE1") (class "Default")
      (node (ref "R27") (pin "2") (pinfunction "2_2") (pintype "passive"))
      (node (ref "U1") (pin "AB22") (pinfunction "DRAM_SDCKE1_AB22") (pintype "output"))
      (node (ref "U5") (pin "J9") (pinfunction "NC_J9_J9") (pintype "passive"))
      (node (ref "U6") (pin "J9") (pinfunction "NC_J9_J9") (pintype "passive"))
    )
    (net (code "69") (name "/DRAM_SDCLK0_N") (class "Default")
      (node (ref "R116") (pin "2") (pinfunction "2_2") (pintype "passive"))
      (node (ref "U5") (pin "K7") (pinfunction "~{CK}_K7") (pintype "input"))
      (node (ref "U6") (pin "K7") (pinfunction "~{CK}_K7") (pintype "input"))
    )
    (net (code "70") (name "/DRAM_SDCLK0_P") (class "Default")
      (node (ref "R117") (pin "2") (pinfunction "2_2") (pintype "passive"))
      (node (ref "U5") (pin "J7") (pinfunction "CK_J7") (pintype "input"))
      (node (ref "U6") (pin "J7") (pinfunction "CK_J7") (pintype "input"))
    )
    (net (code "71") (name "/DRAM_SDQS0_N") (class "Default")
      (node (ref "U1") (pin "AD21") (pinfunction "DRAM_SDQS0_N_AD21") (pintype "bidirectional"))
      (node (ref "U5") (pin "B7") (pinfunction "~{UDQ}S_B7") (pintype "bidirectional"))
    )
    (net (code "72") (name "/DRAM_SDQS0_P") (class "Default")
      (node (ref "U1") (pin "AE21") (pinfunction "DRAM_SDQS0_P_AE21") (pintype "bidirectional"))
      (node (ref "U5") (pin "C7") (pinfunction "UDQS_C7") (pintype "bidirectional"))
    )
    (net (code "73") (name "/DRAM_SDQS1_N") (class "Default")
      (node (ref "U1") (pin "AE15") (pinfunction "DRAM_SDQS1_N_AE15") (pintype "bidirectional"))
      (node (ref "U5") (pin "G3") (pinfunction "~{LDQ}S_G3") (pintype "bidirectional"))
    )
    (net (code "74") (name "/DRAM_SDQS1_P") (class "Default")
      (node (ref "U1") (pin "AD15") (pinfunction "DRAM_SDQS1_P_AD15") (pintype "bidirectional"))
      (node (ref "U5") (pin "F3") (pinfunction "LDQS_F3") (pintype "bidirectional"))
    )
    (net (code "75") (name "/DRAM_SDQS2_N") (class "Default")
      (node (ref "U1") (pin "Y25") (pinfunction "DRAM_SDQS2_N_Y25") (pintype "bidirectional"))
      (node (ref "U6") (pin "B7") (pinfunction "~{UDQ}S_B7") (pintype "bidirectional"))
    )
    (net (code "76") (name "/DRAM_SDQS2_P") (class "Default")
      (node (ref "U1") (pin "Y24") (pinfunction "DRAM_SDQS2_P_Y24") (pintype "bidirectional"))
      (node (ref "U6") (pin "C7") (pinfunction "UDQS_C7") (pintype "bidirectional"))
    )
    (net (code "77") (name "/DRAM_SDQS3_N") (class "Default")
      (node (ref "U1") (pin "T25") (pinfunction "DRAM_SDQS3_N_T25") (pintype "bidirectional"))
      (node (ref "U6") (pin "G3") (pinfunction "~{LDQ}S_G3") (pintype "bidirectional"))
    )
    (net (code "78") (name "/DRAM_SDQS3_P") (class "Default")
      (node (ref "U1") (pin "T24") (pinfunction "DRAM_SDQS3_P_T24") (pintype "bidirectional"))
      (node (ref "U6") (pin "F3") (pinfunction "LDQS_F3") (pintype "bidirectional"))
    )
    (net (code "79") (name "/DRAM_SDWE_B") (class "Default")
      (node (ref "U1") (pin "AB14") (pinfunction "~{DRAM_SDWE_B}_AB14") (pintype "output"))
      (node (ref "U5") (pin "L3") (pinfunction "~{WE}_L3") (pintype "input"))
      (node (ref "U6") (pin "L3") (pinfunction "~{WE}_L3") (pintype "input"))
    )
    (net (code "80") (name "DDR_VREF") (class "Default")
      (node (ref "C85") (pin "2") (pinfunction "2_2") (pintype "passive"))
      (node (ref "C86") (pin "2") (pinfunction "2_2") (pintype "passive"))
      (node (ref "C87") (pin "2") (pinfunction "2_2") (pintype "passive"))
      (node (ref "C88") (pin "2") (pinfunction "2_2") (pintype "passive"))
      (node (ref "C90") (pin "2") (pinfunction "2_2") (pintype "passive"))
      (node (ref "U1") (pin "AC13") (pinfunction "DRAM_VREF_AC13") (pintype "power_in"))
      (node (ref "U5") (pin "H1") (pinfunction "VREFDQ_H1") (pintype "input"))
      (node (ref "U5") (pin "M8") (pinfunction "VREFCA_M8") (pintype "input"))
      (node (ref "U6") (pin "H1") (pinfunction "VREFDQ_H1") (pintype "input"))
      (node (ref "U6") (pin "M8") (pinfunction "VREFCA_M8") (pintype "input"))
    )
    (net (code "81") (name "GND") (class "Default")
      (node (ref "C100") (pin "1") (pinfunction "1_1") (pintype "passive"))
      (node (ref "C101") (pin "1") (pinfunction "1_1") (pintype "passive"))
      (node (ref "C102") (pin "1") (pinfunction "1_1") (pintype "passive"))
      (node (ref "C103") (pin "1") (pinfunction "1_1") (pintype "passive"))
      (node (ref "C104") (pin "1") (pinfunction "1_1") (pintype "passive"))
      (node (ref "C105") (pin "1") (pinfunction "1_1") (pintype "passive"))
      (node (ref "C106") (pin "1") (pinfunction "1_1") (pintype "passive"))
      (node (ref "C108") (pin "1") (pinfunction "1_1") (pintype "passive"))
      (node (ref "C109") (pin "1") (pinfunction "1_1") (pintype "passive"))
      (node (ref "C110") (pin "1") (pinfunction "1_1") (pintype "passive"))
      (node (ref "C111") (pin "1") (pinfunction "1_1") (pintype "passive"))
      (node (ref "C112") (pin "1") (pinfunction "1_1") (pintype "passive"))
      (node (ref "C113") (pin "1") (pinfunction "1_1") (pintype "passive"))
      (node (ref "C114") (pin "1") (pinfunction "1_1") (pintype "passive"))
      (node (ref "C115") (pin "1") (pinfunction "1_1") (pintype "passive"))
      (node (ref "C116") (pin "1") (pinfunction "1_1") (pintype "passive"))
      (node (ref "C117") (pin "1") (pinfunction "1_1") (pintype "passive"))
      (node (ref "C118") (pin "1") (pinfunction "1_1") (pintype "passive"))
      (node (ref "C119") (pin "1") (pinfunction "1_1") (pintype "passive"))
      (node (ref "C120") (pin "1") (pinfunction "1_1") (pintype "passive"))
      (node (ref "C121") (pin "1") (pinfunction "1_1") (pintype "passive"))
      (node (ref "C122") (pin "1") (pinfunction "1_1") (pintype "passive"))
      (node (ref "C123") (pin "1") (pinfunction "1_1") (pintype "passive"))
      (node (ref "C124") (pin "1") (pinfunction "1_1") (pintype "passive"))
      (node (ref "C125") (pin "1") (pinfunction "1_1") (pintype "passive"))
      (node (ref "C85") (pin "1") (pinfunction "1_1") (pintype "passive"))
      (node (ref "C86") (pin "1") (pinfunction "1_1") (pintype "passive"))
      (node (ref "C87") (pin "1") (pinfunction "1_1") (pintype "passive"))
      (node (ref "C88") (pin "1") (pinfunction "1_1") (pintype "passive"))
      (node (ref "C89") (pin "1") (pinfunction "1_1") (pintype "passive"))
      (node (ref "C90") (pin "1") (pinfunction "1_1") (pintype "passive"))
      (node (ref "C91") (pin "1") (pinfunction "1_1") (pintype "passive"))
      (node (ref "C92") (pin "1") (pinfunction "1_1") (pintype "passive"))
      (node (ref "C93") (pin "1") (pinfunction "1_1") (pintype "passive"))
      (node (ref "C94") (pin "1") (pinfunction "1_1") (pintype "passive"))
      (node (ref "C95") (pin "1") (pinfunction "1_1") (pintype "passive"))
      (node (ref "C96") (pin "1") (pinfunction "1_1") (pintype "passive"))
      (node (ref "C97") (pin "1") (pinfunction "1_1") (pintype "passive"))
      (node (ref "C98") (pin "1") (pinfunction "1_1") (pintype "passive"))
      (node (ref "C99") (pin "1") (pinfunction "1_1") (pintype "passive"))
      (node (ref "R27") (pin "1") (pinfunction "1_1") (pintype "passive"))
      (node (ref "R28") (pin "1") (pinfunction "1_1") (pintype "passive"))
      (node (ref "R29") (pin "1") (pinfunction "1_1") (pintype "passive"))
      (node (ref "R30") (pin "1") (pinfunction "1_1") (pintype "passive"))
      (node (ref "R31") (pin "1") (pinfunction "1_1") (pintype "passive"))
      (node (ref "R32") (pin "1") (pinfunction "1_1") (pintype "passive"))
      (node (ref "R33") (pin "1") (pinfunction "1_1") (pintype "passive"))
      (node (ref "R34") (pin "1") (pinfunction "1_1") (pintype "passive"))
      (node (ref "U5") (pin "A9") (pinfunction "VSS1_A9") (pintype "power_in"))
      (node (ref "U5") (pin "B1") (pinfunction "VSSQ1_B1") (pintype "power_in"))
      (node (ref "U5") (pin "B3") (pinfunction "VSS2_B3") (pintype "power_in"))
      (node (ref "U5") (pin "B9") (pinfunction "VSSQ2_B9") (pintype "power_in"))
      (node (ref "U5") (pin "D1") (pinfunction "VSSQ3_D1") (pintype "power_in"))
      (node (ref "U5") (pin "D8") (pinfunction "VSSQ4_D8") (pintype "power_in"))
      (node (ref "U5") (pin "E1") (pinfunction "VSS3_E1") (pintype "power_in"))
      (node (ref "U5") (pin "E2") (pinfunction "VSSQ5_E2") (pintype "power_in"))
      (node (ref "U5") (pin "E8") (pinfunction "VSSQ6_E8") (pintype "power_in"))
      (node (ref "U5") (pin "F9") (pinfunction "VSSQ7_F9") (pintype "power_in"))
      (node (ref "U5") (pin "G1") (pinfunction "VSSQ8_G1") (pintype "power_in"))
      (node (ref "U5") (pin "G8") (pinfunction "VSS4_G8") (pintype "power_in"))
      (node (ref "U5") (pin "G9") (pinfunction "VSSQ9_G9") (pintype "power_in"))
      (node (ref "U5") (pin "J2") (pinfunction "VSS5_J2") (pintype "power_in"))
      (node (ref "U5") (pin "J8") (pinfunction "VSS6_J8") (pintype "power_in"))
      (node (ref "U5") (pin "M1") (pinfunction "VSS7_M1") (pintype "power_in"))
      (node (ref "U5") (pin "M9") (pinfunction "VSS8_M9") (pintype "power_in"))
      (node (ref "U5") (pin "P1") (pinfunction "VSS9_P1") (pintype "power_in"))
      (node (ref "U5") (pin "P9") (pinfunction "VSS10_P9") (pintype "power_in"))
      (node (ref "U5") (pin "T1") (pinfunction "VSS11_T1") (pintype "power_in"))
      (node (ref "U5") (pin "T9") (pinfunction "VSS12_T9") (pintype "power_in"))
      (node (ref "U6") (pin "A9") (pinfunction "VSS1_A9") (pintype "power_in"))
      (node (ref "U6") (pin "B1") (pinfunction "VSSQ1_B1") (pintype "power_in"))
      (node (ref "U6") (pin "B3") (pinfunction "VSS2_B3") (pintype "power_in"))
      (node (ref "U6") (pin "B9") (pinfunction "VSSQ2_B9") (pintype "power_in"))
      (node (ref "U6") (pin "D1") (pinfunction "VSSQ3_D1") (pintype "power_in"))
      (node (ref "U6") (pin "D8") (pinfunction "VSSQ4_D8") (pintype "power_in"))
      (node (ref "U6") (pin "E1") (pinfunction "VSS3_E1") (pintype "power_in"))
      (node (ref "U6") (pin "E2") (pinfunction "VSSQ5_E2") (pintype "power_in"))
      (node (ref "U6") (pin "E8") (pinfunction "VSSQ6_E8") (pintype "power_in"))
      (node (ref "U6") (pin "F9") (pinfunction "VSSQ7_F9") (pintype "power_in"))
      (node (ref "U6") (pin "G1") (pinfunction "VSSQ8_G1") (pintype "power_in"))
      (node (ref "U6") (pin "G8") (pinfunction "VSS4_G8") (pintype "power_in"))
      (node (ref "U6") (pin "G9") (pinfunction "VSSQ9_G9") (pintype "power_in"))
      (node (ref "U6") (pin "J2") (pinfunction "VSS5_J2") (pintype "power_in"))
      (node (ref "U6") (pin "J8") (pinfunction "VSS6_J8") (pintype "power_in"))
      (node (ref "U6") (pin "M1") (pinfunction "VSS7_M1") (pintype "power_in"))
      (node (ref "U6") (pin "M9") (pinfunction "VSS8_M9") (pintype "power_in"))
      (node (ref "U6") (pin "P1") (pinfunction "VSS9_P1") (pintype "power_in"))
      (node (ref "U6") (pin "P9") (pinfunction "VSS10_P9") (pintype "power_in"))
      (node (ref "U6") (pin "T1") (pinfunction "VSS11_T1") (pintype "power_in"))
      (node (ref "U6") (pin "T9") (pinfunction "VSS12_T9") (pintype "power_in"))
    )
    (net (code "82") (name "NVCC_DRAM") (class "Default")
      (node (ref "C100") (pin "2") (pinfunction "2_2") (pintype "passive"))
      (node (ref "C101") (pin "2") (pinfunction "2_2") (pintype "passive"))
      (node (ref "C102") (pin "2") (pinfunction "2_2") (pintype "passive"))
      (node (ref "C103") (pin "2") (pinfunction "2_2") (pintype "passive"))
      (node (ref "C104") (pin "2") (pinfunction "2_2") (pintype "passive"))
      (node (ref "C105") (pin "2") (pinfunction "2_2") (pintype "passive"))
      (node (ref "C106") (pin "2") (pinfunction "2_2") (pintype "passive"))
      (node (ref "C108") (pin "2") (pinfunction "2_2") (pintype "passive"))
      (node (ref "C109") (pin "2") (pinfunction "2_2") (pintype "passive"))
      (node (ref "C110") (pin "2") (pinfunction "2_2") (pintype "passive"))
      (node (ref "C111") (pin "2") (pinfunction "2_2") (pintype "passive"))
      (node (ref "C112") (pin "2") (pinfunction "2_2") (pintype "passive"))
      (node (ref "C113") (pin "2") (pinfunction "2_2") (pintype "passive"))
      (node (ref "C114") (pin "2") (pinfunction "2_2") (pintype "passive"))
      (node (ref "C115") (pin "2") (pinfunction "2_2") (pintype "passive"))
      (node (ref "C116") (pin "2") (pinfunction "2_2") (pintype "passive"))
      (node (ref "C117") (pin "2") (pinfunction "2_2") (pintype "passive"))
      (node (ref "C118") (pin "2") (pinfunction "2_2") (pintype "passive"))
      (node (ref "C119") (pin "2") (pinfunction "2_2") (pintype "passive"))
      (node (ref "C120") (pin "2") (pinfunction "2_2") (pintype "passive"))
      (node (ref "C121") (pin "2") (pinfunction "2_2") (pintype "passive"))
      (node (ref "C122") (pin "2") (pinfunction "2_2") (pintype "passive"))
      (node (ref "C123") (pin "2") (pinfunction "2_2") (pintype "passive"))
      (node (ref "C124") (pin "2") (pinfunction "2_2") (pintype "passive"))
      (node (ref "C125") (pin "2") (pinfunction "2_2") (pintype "passive"))
      (node (ref "C89") (pin "2") (pinfunction "2_2") (pintype "passive"))
      (node (ref "C91") (pin "2") (pinfunction "2_2") (pintype "passive"))
      (node (ref "C92") (pin "2") (pinfunction "2_2") (pintype "passive"))
      (node (ref "C93") (pin "2") (pinfunction "2_2") (pintype "passive"))
      (node (ref "C94") (pin "2") (pinfunction "2_2") (pintype "passive"))
      (node (ref "C95") (pin "2") (pinfunction "2_2") (pintype "passive"))
      (node (ref "C96") (pin "2") (pinfunction "2_2") (pintype "passive"))
      (node (ref "C97") (pin "2") (pinfunction "2_2") (pintype "passive"))
      (node (ref "C98") (pin "2") (pinfunction "2_2") (pintype "passive"))
      (node (ref "C99") (pin "2") (pinfunction "2_2") (pintype "passive"))
      (node (ref "U1") (pin "AA16") (pinfunction "NVCC_DRAM_06_AA16") (pintype "power_in"))
      (node (ref "U1") (pin "AA17") (pinfunction "NVCC_DRAM_07_AA17") (pintype "power_in"))
      (node (ref "U1") (pin "AA18") (pinfunction "NVCC_DRAM_08_AA18") (pintype "power_in"))
      (node (ref "U1") (pin "AA19") (pinfunction "NVCC_DRAM_09_AA19") (pintype "power_in"))
      (node (ref "U1") (pin "AA20") (pinfunction "NVCC_DRAM_10_AA20") (pintype "power_in"))
      (node (ref "U1") (pin "AA21") (pinfunction "NVCC_DRAM_11_AA21") (pintype "power_in"))
      (node (ref "U1") (pin "T21") (pinfunction "NVCC_DRAM_01_T21") (pintype "power_in"))
      (node (ref "U1") (pin "U21") (pinfunction "NVCC_DRAM_02_U21") (pintype "power_in"))
      (node (ref "U1") (pin "V21") (pinfunction "NVCC_DRAM_03_V21") (pintype "power_in"))
      (node (ref "U1") (pin "W21") (pinfunction "NVCC_DRAM_04_W21") (pintype "power_in"))
      (node (ref "U1") (pin "Y20") (pinfunction "NVCC_DRAM_CKE_Y20") (pintype "power_in"))
      (node (ref "U1") (pin "Y21") (pinfunction "NVCC_DRAM_05_Y21") (pintype "power_in"))
      (node (ref "U5") (pin "A1") (pinfunction "VDDQ1_A1") (pintype "power_in"))
      (node (ref "U5") (pin "A8") (pinfunction "VDDQ2_A8") (pintype "power_in"))
      (node (ref "U5") (pin "B2") (pinfunction "VDD1_B2") (pintype "power_in"))
      (node (ref "U5") (pin "C1") (pinfunction "VDDQ3_C1") (pintype "power_in"))
      (node (ref "U5") (pin "C9") (pinfunction "VDDQ4_C9") (pintype "power_in"))
      (node (ref "U5") (pin "D2") (pinfunction "VDDQ5_D2") (pintype "power_in"))
      (node (ref "U5") (pin "D9") (pinfunction "VDD2_D9") (pintype "power_in"))
      (node (ref "U5") (pin "E9") (pinfunction "VDDQ6_E9") (pintype "power_in"))
      (node (ref "U5") (pin "F1") (pinfunction "VDDQ7_F1") (pintype "power_in"))
      (node (ref "U5") (pin "G7") (pinfunction "VDD3_G7") (pintype "power_in"))
      (node (ref "U5") (pin "H2") (pinfunction "VDDQ8_H2") (pintype "power_in"))
      (node (ref "U5") (pin "H9") (pinfunction "VDDQ9_H9") (pintype "power_in"))
      (node (ref "U5") (pin "K2") (pinfunction "VDD4_K2") (pintype "power_in"))
      (node (ref "U5") (pin "K8") (pinfunction "VDD5_K8") (pintype "power_in"))
      (node (ref "U5") (pin "N1") (pinfunction "VDD6_N1") (pintype "power_in"))
      (node (ref "U5") (pin "N9") (pinfunction "VDD7_N9") (pintype "power_in"))
      (node (ref "U5") (pin "R1") (pinfunction "VDD8_R1") (pintype "power_in"))
      (node (ref "U5") (pin "R9") (pinfunction "VDD9_R9") (pintype "power_in"))
      (node (ref "U6") (pin "A1") (pinfunction "VDDQ1_A1") (pintype "power_in"))
      (node (ref "U6") (pin "A8") (pinfunction "VDDQ2_A8") (pintype "power_in"))
      (node (ref "U6") (pin "B2") (pinfunction "VDD1_B2") (pintype "power_in"))
      (node (ref "U6") (pin "C1") (pinfunction "VDDQ3_C1") (pintype "power_in"))
      (node (ref "U6") (pin "C9") (pinfunction "VDDQ4_C9") (pintype "power_in"))
      (node (ref "U6") (pin "D2") (pinfunction "VDDQ5_D2") (pintype "power_in"))
      (node (ref "U6") (pin "D9") (pinfunction "VDD2_D9") (pintype "power_in"))
      (node (ref "U6") (pin "E9") (pinfunction "VDDQ6_E9") (pintype "power_in"))
      (node (ref "U6") (pin "F1") (pinfunction "VDDQ7_F1") (pintype "power_in"))
      (node (ref "U6") (pin "G7") (pinfunction "VDD3_G7") (pintype "power_in"))
      (node (ref "U6") (pin "H2") (pinfunction "VDDQ8_H2") (pintype "power_in"))
      (node (ref "U6") (pin "H9") (pinfunction "VDDQ9_H9") (pintype "power_in"))
      (node (ref "U6") (pin "K2") (pinfunction "VDD4_K2") (pintype "power_in"))
      (node (ref "U6") (pin "K8") (pinfunction "VDD5_K8") (pintype "power_in"))
      (node (ref "U6") (pin "N1") (pinfunction "VDD6_N1") (pintype "power_in"))
      (node (ref "U6") (pin "N9") (pinfunction "VDD7_N9") (pintype "power_in"))
      (node (ref "U6") (pin "R1") (pinfunction "VDD8_R1") (pintype "power_in"))
      (node (ref "U6") (pin "R9") (pinfunction "VDD9_R9") (pintype "power_in"))
    )
    (net (code "83") (name "Net-(U1E-DRAM_ZQPAD)") (class "Default")
      (node (ref "R34") (pin "2") (pinfunction "2_2") (pintype "passive"))
      (node (ref "U1") (pin "AB13") (pinfunction "DRAM_ZQPAD_AB13") (pintype "bidirectional"))
    )
    (net (code "84") (name "Net-(U5-NC_L9)") (class "Default")
      (node (ref "R29") (pin "2") (pinfunction "2_2") (pintype "passive"))
      (node (ref "U5") (pin "L9") (pinfunction "NC_L9_L9") (pintype "passive"))
    )
    (net (code "85") (name "Net-(U5-ZQ)") (class "Default")
      (node (ref "R32") (pin "2") (pinfunction "2_2") (pintype "passive"))
      (node (ref "U5") (pin "L8") (pinfunction "ZQ_L8") (pintype "input"))
    )
    (net (code "86") (name "Net-(U6-NC_L9)") (class "Default")
      (node (ref "R30") (pin "2") (pinfunction "2_2") (pintype "passive"))
      (node (ref "U6") (pin "L9") (pinfunction "NC_L9_L9") (pintype "passive"))
    )
    (net (code "87") (name "Net-(U6-ZQ)") (class "Default")
      (node (ref "R33") (pin "2") (pinfunction "2_2") (pintype "passive"))
      (node (ref "U6") (pin "L8") (pinfunction "ZQ_L8") (pintype "input"))
    )
  )
)
